# main.net
KiCad netlist of a schematic drawn in EAGLE
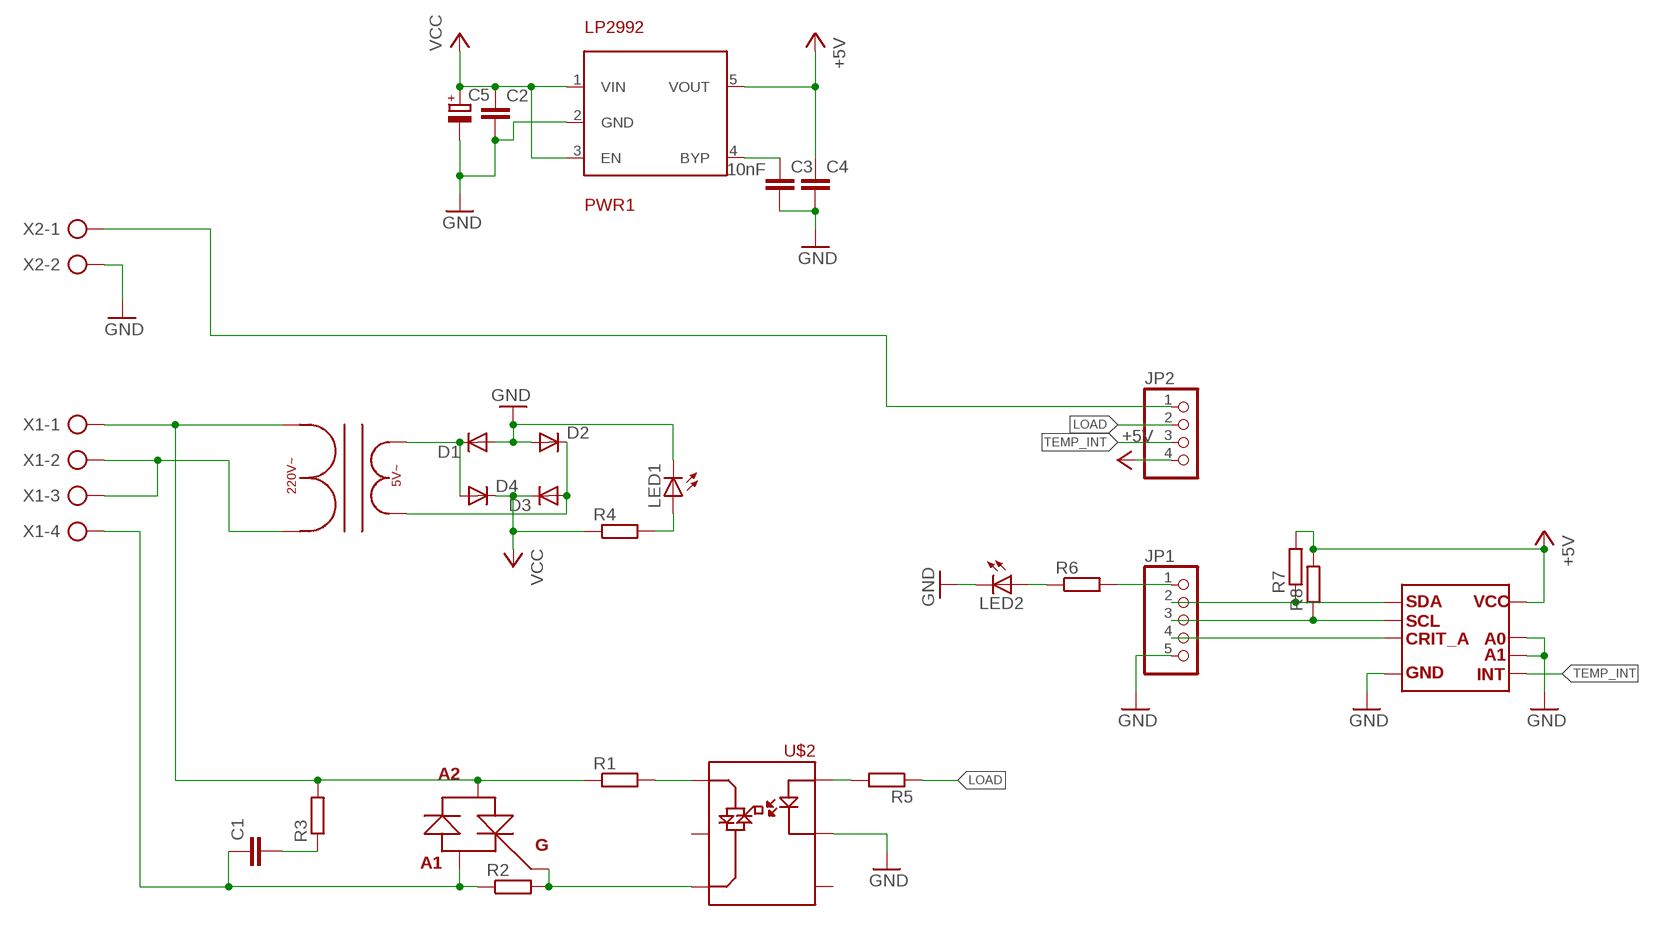
[diagram p0: schematic, sheet 1]

(export (version "E")
  (design (tool "Eeschema 10.0.6"))
  (components
    (comp (ref "C1")
      (value "C-EU075-052X106")
      (footprint "eagle-import:C075-052X106")
      (libsource (lib "eagle-import") (part "C-EU075-052X106"))
    )
    (comp (ref "C2")
      (value "C-EUC0805")
      (footprint "eagle-import:C0805")
      (libsource (lib "eagle-import") (part "C-EUC0805"))
    )
    (comp (ref "C3")
      (value "C-EUC0805")
      (footprint "eagle-import:C0805")
      (libsource (lib "eagle-import") (part "C-EUC0805"))
    )
    (comp (ref "C4")
      (value "C-EUC0805")
      (footprint "eagle-import:C0805")
      (libsource (lib "eagle-import") (part "C-EUC0805"))
    )
    (comp (ref "C5")
      (value "CPOL-EUSMCA")
      (footprint "eagle-import:SMC_A")
      (libsource (lib "eagle-import") (part "CPOL-EUSMCA"))
    )
    (comp (ref "D1")
      (value "DIODE-DO-214AC")
      (footprint "eagle-import:DO-214AC")
      (libsource (lib "eagle-import") (part "DIODE-DO-214AC"))
    )
    (comp (ref "D2")
      (value "DIODE-DO-214AC")
      (footprint "eagle-import:DO-214AC")
      (libsource (lib "eagle-import") (part "DIODE-DO-214AC"))
    )
    (comp (ref "D3")
      (value "DIODE-DO-214AC")
      (footprint "eagle-import:DO-214AC")
      (libsource (lib "eagle-import") (part "DIODE-DO-214AC"))
    )
    (comp (ref "D4")
      (value "DIODE-DO-214AC")
      (footprint "eagle-import:DO-214AC")
      (libsource (lib "eagle-import") (part "DIODE-DO-214AC"))
    )
    (comp (ref "JP1")
      (value "PINHD-1X5")
      (footprint "eagle-import:1X05")
      (libsource (lib "eagle-import") (part "PINHD-1X5"))
    )
    (comp (ref "JP2")
      (value "PINHD-1X4")
      (footprint "eagle-import:1X04")
      (libsource (lib "eagle-import") (part "PINHD-1X4"))
    )
    (comp (ref "LED1")
      (value "LED3MM")
      (footprint "eagle-import:LED3MM")
      (libsource (lib "eagle-import") (part "LED3MM"))
    )
    (comp (ref "LED2")
      (value "LED3MM")
      (footprint "eagle-import:LED3MM")
      (libsource (lib "eagle-import") (part "LED3MM"))
    )
    (comp (ref "PWR1")
      (value "LP2992")
      (footprint "eagle-import:SOT23-5")
      (libsource (lib "eagle-import") (part "LP2992"))
    )
    (comp (ref "R1")
      (value "R-EU_M1206")
      (footprint "eagle-import:M1206")
      (libsource (lib "eagle-import") (part "R-EU_M1206"))
    )
    (comp (ref "R2")
      (value "R-EU_M1206")
      (footprint "eagle-import:M1206")
      (libsource (lib "eagle-import") (part "R-EU_M1206"))
    )
    (comp (ref "R3")
      (value "R-EU_M1206")
      (footprint "eagle-import:M1206")
      (libsource (lib "eagle-import") (part "R-EU_M1206"))
    )
    (comp (ref "R4")
      (value "R-EU_M0805")
      (footprint "eagle-import:M0805")
      (libsource (lib "eagle-import") (part "R-EU_M0805"))
    )
    (comp (ref "R5")
      (value "R-EU_M0805")
      (footprint "eagle-import:M0805")
      (libsource (lib "eagle-import") (part "R-EU_M0805"))
    )
    (comp (ref "R6")
      (value "R-EU_M0805")
      (footprint "eagle-import:M0805")
      (libsource (lib "eagle-import") (part "R-EU_M0805"))
    )
    (comp (ref "R7")
      (value "R-EU_M0805")
      (footprint "eagle-import:M0805")
      (libsource (lib "eagle-import") (part "R-EU_M0805"))
    )
    (comp (ref "R8")
      (value "R-EU_M0805")
      (footprint "eagle-import:M0805")
      (libsource (lib "eagle-import") (part "R-EU_M0805"))
    )
    (comp (ref "TMP1")
      (value "LM92")
      (footprint "eagle-import:SOIC8-1.27-5X4MM")
      (libsource (lib "eagle-import") (part "LM92"))
    )
    (comp (ref "U$1")
      (value "ТПГ-0.7-5V")
      (footprint "eagle-import:TPG-0.7-5V")
      (libsource (lib "eagle-import") (part "ТПГ-0.7-5V"))
    )
    (comp (ref "U$2")
      (value "MOC3043")
      (footprint "eagle-import:DIL06")
      (libsource (lib "eagle-import") (part "MOC3043"))
    )
    (comp (ref "U$3")
      (value "BTB16")
      (footprint "eagle-import:TO220NORM")
      (libsource (lib "eagle-import") (part "BTB16"))
    )
    (comp (ref "X1")
      (value "AK500/4")
      (footprint "eagle-import:AK500_4")
      (libsource (lib "eagle-import") (part "AK500/4"))
    )
    (comp (ref "X2")
      (value "AK500/2")
      (footprint "eagle-import:AK500_2")
      (libsource (lib "eagle-import") (part "AK500/2"))
    )
  )
  (nets
    (net (code "1") (name "+5V") (class "Default")
      (node (ref "C4") (pin "1") (pinfunction "1_1") (pintype "passive"))
      (node (ref "JP2") (pin "4") (pinfunction "4_4") (pintype "passive"))
      (node (ref "PWR1") (pin "5") (pinfunction "VOUT_5") (pintype "bidirectional"))
      (node (ref "R7") (pin "2") (pinfunction "2_2") (pintype "passive"))
      (node (ref "R8") (pin "2") (pinfunction "2_2") (pintype "passive"))
      (node (ref "TMP1") (pin "8") (pinfunction "OUT_8") (pintype "bidirectional"))
    )
    (net (code "2") (name "GND") (class "Default")
      (node (ref "C2") (pin "2") (pinfunction "2_2") (pintype "passive"))
      (node (ref "C3") (pin "2") (pinfunction "2_2") (pintype "passive"))
      (node (ref "C4") (pin "2") (pinfunction "2_2") (pintype "passive"))
      (node (ref "C5") (pin "-") (pinfunction "-_-") (pintype "passive"))
      (node (ref "D1") (pin "A") (pinfunction "A_A") (pintype "passive"))
      (node (ref "D2") (pin "A") (pinfunction "A_A") (pintype "passive"))
      (node (ref "JP1") (pin "5") (pinfunction "5_5") (pintype "passive"))
      (node (ref "LED1") (pin "K") (pinfunction "C_K") (pintype "passive"))
      (node (ref "LED2") (pin "K") (pinfunction "C_K") (pintype "passive"))
      (node (ref "PWR1") (pin "2") (pinfunction "GND_2") (pintype "bidirectional"))
      (node (ref "TMP1") (pin "4") (pinfunction "OUT_4") (pintype "bidirectional"))
      (node (ref "TMP1") (pin "6") (pinfunction "OUT_6") (pintype "bidirectional"))
      (node (ref "TMP1") (pin "7") (pinfunction "OUT_7") (pintype "bidirectional"))
      (node (ref "U$2") (pin "2") (pinfunction "LED_OUT_2") (pintype "bidirectional"))
      (node (ref "X2") (pin "2") (pinfunction "KL_2") (pintype "passive"))
    )
    (net (code "3") (name "LOAD") (class "Default")
      (node (ref "JP2") (pin "2") (pinfunction "2_2") (pintype "passive"))
      (node (ref "R5") (pin "1") (pinfunction "1_1") (pintype "passive"))
    )
    (net (code "4") (name "Net-(C1-Pad2)") (class "Default")
      (node (ref "C1") (pin "2") (pinfunction "2_2") (pintype "passive"))
      (node (ref "R3") (pin "1") (pinfunction "1_1") (pintype "passive"))
    )
    (net (code "5") (name "Net-(D1-PadC)") (class "Default")
      (node (ref "D1") (pin "C") (pinfunction "C_C") (pintype "passive"))
      (node (ref "D4") (pin "A") (pinfunction "A_A") (pintype "passive"))
      (node (ref "U$1") (pin "DC2") (pinfunction "DC2_DC2") (pintype "bidirectional"))
    )
    (net (code "6") (name "Net-(D2-PadC)") (class "Default")
      (node (ref "D2") (pin "C") (pinfunction "C_C") (pintype "passive"))
      (node (ref "D3") (pin "A") (pinfunction "A_A") (pintype "passive"))
      (node (ref "U$1") (pin "DC1") (pinfunction "DC1_DC1") (pintype "bidirectional"))
    )
    (net (code "7") (name "Net-(JP1-Pad1)") (class "Default")
      (node (ref "JP1") (pin "1") (pinfunction "1_1") (pintype "passive"))
      (node (ref "R6") (pin "2") (pinfunction "2_2") (pintype "passive"))
    )
    (net (code "8") (name "Net-(JP1-Pad2)") (class "Default")
      (node (ref "JP1") (pin "2") (pinfunction "2_2") (pintype "passive"))
      (node (ref "R7") (pin "1") (pinfunction "1_1") (pintype "passive"))
      (node (ref "TMP1") (pin "1") (pinfunction "OUT_1") (pintype "bidirectional"))
    )
    (net (code "9") (name "Net-(JP1-Pad3)") (class "Default")
      (node (ref "JP1") (pin "3") (pinfunction "3_3") (pintype "passive"))
      (node (ref "R8") (pin "1") (pinfunction "1_1") (pintype "passive"))
      (node (ref "TMP1") (pin "2") (pinfunction "OUT_2") (pintype "bidirectional"))
    )
    (net (code "10") (name "Net-(JP1-Pad4)") (class "Default")
      (node (ref "JP1") (pin "4") (pinfunction "4_4") (pintype "passive"))
      (node (ref "TMP1") (pin "3") (pinfunction "OUT_3") (pintype "bidirectional"))
    )
    (net (code "11") (name "Net-(LED1-PadA)") (class "Default")
      (node (ref "LED1") (pin "A") (pinfunction "A_A") (pintype "passive"))
      (node (ref "R4") (pin "2") (pinfunction "2_2") (pintype "passive"))
    )
    (net (code "12") (name "Net-(LED2-PadA)") (class "Default")
      (node (ref "LED2") (pin "A") (pinfunction "A_A") (pintype "passive"))
      (node (ref "R6") (pin "1") (pinfunction "1_1") (pintype "passive"))
    )
    (net (code "13") (name "Net-(PWR1-BYP)") (class "Default")
      (node (ref "C3") (pin "1") (pinfunction "1_1") (pintype "passive"))
      (node (ref "PWR1") (pin "4") (pinfunction "BYP_4") (pintype "bidirectional"))
    )
    (net (code "14") (name "Net-(U$2-LED_IN)") (class "Default")
      (node (ref "R5") (pin "2") (pinfunction "2_2") (pintype "passive"))
      (node (ref "U$2") (pin "1") (pinfunction "LED_IN_1") (pintype "bidirectional"))
    )
    (net (code "15") (name "Net-(U$2-SIM1)") (class "Default")
      (node (ref "R1") (pin "2") (pinfunction "2_2") (pintype "passive"))
      (node (ref "U$2") (pin "6") (pinfunction "SIM1_6") (pintype "bidirectional"))
    )
    (net (code "16") (name "Net-(U$2-SIM2)") (class "Default")
      (node (ref "R2") (pin "2") (pinfunction "2_2") (pintype "passive"))
      (node (ref "U$2") (pin "4") (pinfunction "SIM2_4") (pintype "bidirectional"))
      (node (ref "U$3") (pin "GATE") (pinfunction "G_GATE") (pintype "bidirectional"))
    )
    (net (code "17") (name "Net-(U$3-A1)") (class "Default")
      (node (ref "C1") (pin "1") (pinfunction "1_1") (pintype "passive"))
      (node (ref "R2") (pin "1") (pinfunction "1_1") (pintype "passive"))
      (node (ref "U$3") (pin "MT1") (pinfunction "A1_MT1") (pintype "bidirectional"))
      (node (ref "X1") (pin "4") (pinfunction "KL_4") (pintype "passive"))
    )
    (net (code "18") (name "Net-(U$3-A2)") (class "Default")
      (node (ref "R1") (pin "1") (pinfunction "1_1") (pintype "passive"))
      (node (ref "R3") (pin "2") (pinfunction "2_2") (pintype "passive"))
      (node (ref "U$1") (pin "AC2") (pinfunction "AC2_AC2") (pintype "bidirectional"))
      (node (ref "U$3") (pin "MT2") (pinfunction "A2_MT2") (pintype "bidirectional"))
      (node (ref "X1") (pin "1") (pinfunction "KL_1") (pintype "passive"))
    )
    (net (code "19") (name "Net-(X1B-KL)") (class "Default")
      (node (ref "U$1") (pin "AC1") (pinfunction "AC1_AC1") (pintype "bidirectional"))
      (node (ref "X1") (pin "2") (pinfunction "KL_2") (pintype "passive"))
      (node (ref "X1") (pin "3") (pinfunction "KL_3") (pintype "passive"))
    )
    (net (code "20") (name "Net-(X2A-KL)") (class "Default")
      (node (ref "JP2") (pin "1") (pinfunction "1_1") (pintype "passive"))
      (node (ref "X2") (pin "1") (pinfunction "KL_1") (pintype "passive"))
    )
    (net (code "21") (name "TEMP_INT") (class "Default")
      (node (ref "JP2") (pin "3") (pinfunction "3_3") (pintype "passive"))
      (node (ref "TMP1") (pin "5") (pinfunction "OUT_5") (pintype "bidirectional"))
    )
    (net (code "22") (name "VCC") (class "Default")
      (node (ref "C2") (pin "1") (pinfunction "1_1") (pintype "passive"))
      (node (ref "C5") (pin "+") (pinfunction "+_+") (pintype "passive"))
      (node (ref "D3") (pin "C") (pinfunction "C_C") (pintype "passive"))
      (node (ref "D4") (pin "C") (pinfunction "C_C") (pintype "passive"))
      (node (ref "PWR1") (pin "1") (pinfunction "VIN_1") (pintype "bidirectional"))
      (node (ref "PWR1") (pin "3") (pinfunction "EN_3") (pintype "bidirectional"))
      (node (ref "R4") (pin "1") (pinfunction "1_1") (pintype "passive"))
    )
    (net (code "23") (name "unconnected-(U$2-N{slash}C-Pad3)") (class "Default")
      (node (ref "U$2") (pin "3") (pinfunction "N/C_3") (pintype "bidirectional"))
    )
    (net (code "24") (name "unconnected-(U$2-N{slash}C2-Pad5)") (class "Default")
      (node (ref "U$2") (pin "5") (pinfunction "N/C2_5") (pintype "bidirectional"))
    )
  )
)
